# untitled.net
KiCad netlist of a schematic drawn in EAGLE
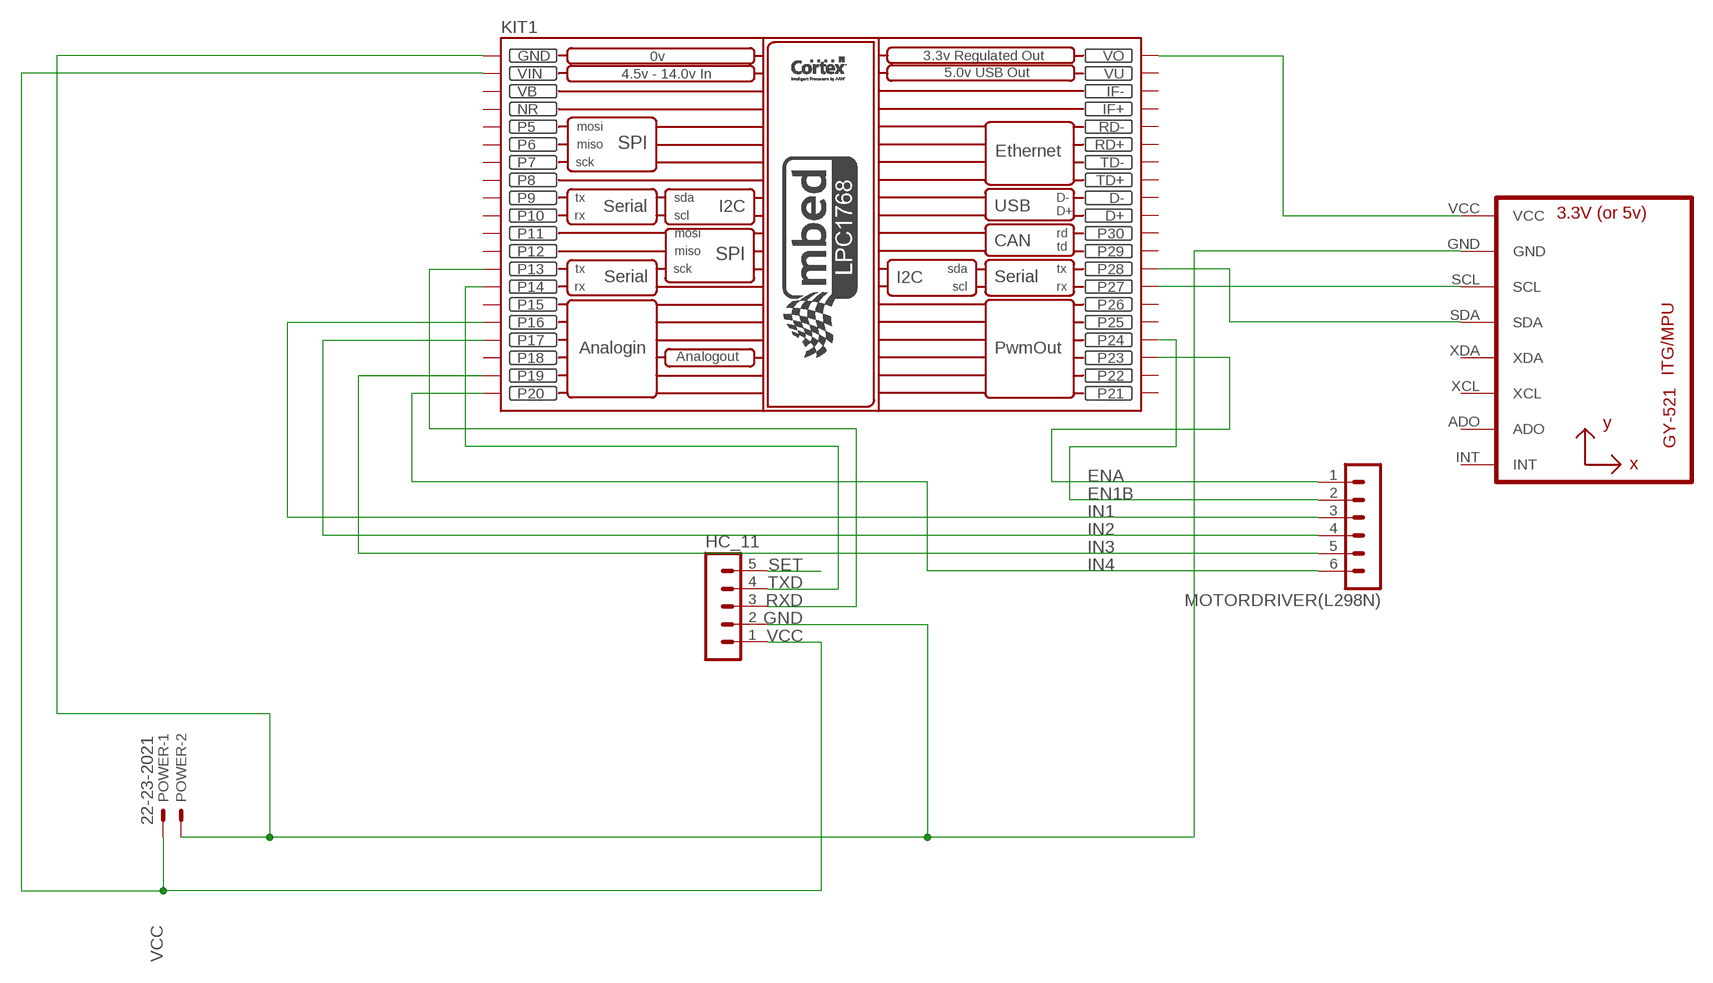
[diagram p0: schematic, sheet 1]

(export (version "E")
  (design (tool "Eeschema 10.0.6"))
  (components
    (comp (ref "HC_11")
      (value "MA05-1")
      (footprint "eagle-import:MA05-1")
      (libsource (lib "eagle-import") (part "MA05-1"))
    )
    (comp (ref "KIT1")
      (value "MBED_NXP_LPC1768")
      (footprint "eagle-import:MBED-KIT")
      (libsource (lib "eagle-import") (part "MBED_NXP_LPC1768"))
    )
    (comp (ref "MOTORDRIVER(L298N)")
      (value "MA06-1")
      (footprint "eagle-import:MA06-1")
      (libsource (lib "eagle-import") (part "MA06-1"))
    )
    (comp (ref "POWER")
      (value "22-23-2021")
      (footprint "eagle-import:22-23-2021")
      (fields (field (name "MF") "MOLEX"))
      (libsource (lib "eagle-import") (part "22-23-2021"))
    )
    (comp (ref "U1")
      (value "GY-521MPU6050")
      (footprint "eagle-import:GY-521")
      (libsource (lib "eagle-import") (part "GY-521MPU6050"))
    )
  )
  (nets
    (net (code "1") (name "/EN1B") (class "Default")
      (node (ref "KIT1") (pin "P$24") (pinfunction "P24_P$24") (pintype "bidirectional"))
      (node (ref "MOTORDRIVER(L298N)") (pin "2") (pinfunction "2_2") (pintype "passive"))
    )
    (net (code "2") (name "/ENA") (class "Default")
      (node (ref "KIT1") (pin "P$23") (pinfunction "P23_P$23") (pintype "bidirectional"))
      (node (ref "MOTORDRIVER(L298N)") (pin "1") (pinfunction "1_1") (pintype "passive"))
    )
    (net (code "3") (name "/GND") (class "Default")
      (node (ref "HC_11") (pin "2") (pinfunction "2_2") (pintype "passive"))
      (node (ref "KIT1") (pin "GND") (pinfunction "GND_GND") (pintype "power_in"))
      (node (ref "POWER") (pin "2") (pinfunction "S_2") (pintype "passive"))
      (node (ref "U1") (pin "GND") (pinfunction "GND_GND") (pintype "bidirectional"))
    )
    (net (code "4") (name "/IN1") (class "Default")
      (node (ref "KIT1") (pin "P$16") (pinfunction "P16_P$16") (pintype "bidirectional"))
      (node (ref "MOTORDRIVER(L298N)") (pin "3") (pinfunction "3_3") (pintype "passive"))
    )
    (net (code "5") (name "/IN2") (class "Default")
      (node (ref "KIT1") (pin "P$17") (pinfunction "P17_P$17") (pintype "bidirectional"))
      (node (ref "MOTORDRIVER(L298N)") (pin "4") (pinfunction "4_4") (pintype "passive"))
    )
    (net (code "6") (name "/IN3") (class "Default")
      (node (ref "KIT1") (pin "P$19") (pinfunction "P19_P$19") (pintype "bidirectional"))
      (node (ref "MOTORDRIVER(L298N)") (pin "5") (pinfunction "5_5") (pintype "passive"))
    )
    (net (code "7") (name "/IN4") (class "Default")
      (node (ref "KIT1") (pin "P$20") (pinfunction "P20_P$20") (pintype "bidirectional"))
      (node (ref "MOTORDRIVER(L298N)") (pin "6") (pinfunction "6_6") (pintype "passive"))
    )
    (net (code "8") (name "/NR") (class "Default")
      (node (ref "KIT1") (pin "NR") (pinfunction "NR_NR") (pintype "power_in"))
    )
    (net (code "9") (name "/RXD") (class "Default")
      (node (ref "HC_11") (pin "3") (pinfunction "3_3") (pintype "passive"))
      (node (ref "KIT1") (pin "P$13") (pinfunction "P13_P$13") (pintype "bidirectional"))
    )
    (net (code "10") (name "/SET") (class "Default")
      (node (ref "HC_11") (pin "5") (pinfunction "5_5") (pintype "passive"))
    )
    (net (code "11") (name "/TXD") (class "Default")
      (node (ref "HC_11") (pin "4") (pinfunction "4_4") (pintype "passive"))
      (node (ref "KIT1") (pin "P$14") (pinfunction "P14_P$14") (pintype "bidirectional"))
    )
    (net (code "12") (name "/VB") (class "Default")
      (node (ref "KIT1") (pin "VB") (pinfunction "VB_VB") (pintype "power_in"))
    )
    (net (code "13") (name "/VCC") (class "Default")
      (node (ref "HC_11") (pin "1") (pinfunction "1_1") (pintype "passive"))
      (node (ref "KIT1") (pin "VIN") (pinfunction "VIN_VIN") (pintype "power_in"))
      (node (ref "POWER") (pin "1") (pinfunction "S_1") (pintype "passive"))
    )
    (net (code "14") (name "/VU") (class "Default")
      (node (ref "KIT1") (pin "VU") (pinfunction "VU_VU") (pintype "power_in"))
    )
    (net (code "15") (name "Net-(KIT1-P27)") (class "Default")
      (node (ref "KIT1") (pin "P$27") (pinfunction "P27_P$27") (pintype "bidirectional"))
      (node (ref "U1") (pin "SCL") (pinfunction "SCL_SCL") (pintype "bidirectional"))
    )
    (net (code "16") (name "Net-(KIT1-P28)") (class "Default")
      (node (ref "KIT1") (pin "P$28") (pinfunction "P28_P$28") (pintype "bidirectional"))
      (node (ref "U1") (pin "SDA") (pinfunction "SDA_SDA") (pintype "bidirectional"))
    )
    (net (code "17") (name "Net-(KIT1-VO)") (class "Default")
      (node (ref "KIT1") (pin "VOUT") (pinfunction "VO_VOUT") (pintype "power_in"))
      (node (ref "U1") (pin "VCC") (pinfunction "VCC_VCC") (pintype "bidirectional"))
    )
    (net (code "18") (name "unconnected-(KIT1-P5-PadP$5)") (class "Default")
      (node (ref "KIT1") (pin "P$5") (pinfunction "P5_P$5") (pintype "bidirectional"))
    )
    (net (code "19") (name "unconnected-(KIT1-P6-PadP$6)") (class "Default")
      (node (ref "KIT1") (pin "P$6") (pinfunction "P6_P$6") (pintype "bidirectional"))
    )
    (net (code "20") (name "unconnected-(KIT1-P7-PadP$7)") (class "Default")
      (node (ref "KIT1") (pin "P$7") (pinfunction "P7_P$7") (pintype "bidirectional"))
    )
    (net (code "21") (name "unconnected-(KIT1-P8-PadP$8)") (class "Default")
      (node (ref "KIT1") (pin "P$8") (pinfunction "P8_P$8") (pintype "bidirectional"))
    )
    (net (code "22") (name "unconnected-(KIT1-P9-PadP$9)") (class "Default")
      (node (ref "KIT1") (pin "P$9") (pinfunction "P9_P$9") (pintype "bidirectional"))
    )
    (net (code "23") (name "unconnected-(KIT1-P10-PadP$10)") (class "Default")
      (node (ref "KIT1") (pin "P$10") (pinfunction "P10_P$10") (pintype "bidirectional"))
    )
    (net (code "24") (name "unconnected-(KIT1-P11-PadP$11)") (class "Default")
      (node (ref "KIT1") (pin "P$11") (pinfunction "P11_P$11") (pintype "bidirectional"))
    )
    (net (code "25") (name "unconnected-(KIT1-P12-PadP$12)") (class "Default")
      (node (ref "KIT1") (pin "P$12") (pinfunction "P12_P$12") (pintype "bidirectional"))
    )
    (net (code "26") (name "unconnected-(KIT1-P15-PadP$15)") (class "Default")
      (node (ref "KIT1") (pin "P$15") (pinfunction "P15_P$15") (pintype "bidirectional"))
    )
    (net (code "27") (name "unconnected-(KIT1-P18-PadP$18)") (class "Default")
      (node (ref "KIT1") (pin "P$18") (pinfunction "P18_P$18") (pintype "bidirectional"))
    )
    (net (code "28") (name "unconnected-(KIT1-P21-PadP$21)") (class "Default")
      (node (ref "KIT1") (pin "P$21") (pinfunction "P21_P$21") (pintype "bidirectional"))
    )
    (net (code "29") (name "unconnected-(KIT1-P22-PadP$22)") (class "Default")
      (node (ref "KIT1") (pin "P$22") (pinfunction "P22_P$22") (pintype "bidirectional"))
    )
    (net (code "30") (name "unconnected-(KIT1-P25-PadP$25)") (class "Default")
      (node (ref "KIT1") (pin "P$25") (pinfunction "P25_P$25") (pintype "bidirectional"))
    )
    (net (code "31") (name "unconnected-(KIT1-P26-PadP$26)") (class "Default")
      (node (ref "KIT1") (pin "P$26") (pinfunction "P26_P$26") (pintype "bidirectional"))
    )
    (net (code "32") (name "unconnected-(KIT1-P29-PadP$29)") (class "Default")
      (node (ref "KIT1") (pin "P$29") (pinfunction "P29_P$29") (pintype "bidirectional"))
    )
    (net (code "33") (name "unconnected-(KIT1-P30-PadP$30)") (class "Default")
      (node (ref "KIT1") (pin "P$30") (pinfunction "P30_P$30") (pintype "bidirectional"))
    )
    (net (code "34") (name "unconnected-(KIT1-PadD+)") (class "Default")
      (node (ref "KIT1") (pin "D+") (pinfunction "D+_D+") (pintype "bidirectional"))
    )
    (net (code "35") (name "unconnected-(KIT1-PadD-)") (class "Default")
      (node (ref "KIT1") (pin "D-") (pinfunction "D-_D-") (pintype "bidirectional"))
    )
    (net (code "36") (name "unconnected-(KIT1-PadIF+)") (class "Default")
      (node (ref "KIT1") (pin "IF+") (pinfunction "IF+_IF+") (pintype "bidirectional"))
    )
    (net (code "37") (name "unconnected-(KIT1-PadIF-)") (class "Default")
      (node (ref "KIT1") (pin "IF-") (pinfunction "IF-_IF-") (pintype "bidirectional"))
    )
    (net (code "38") (name "unconnected-(KIT1-PadRD+)") (class "Default")
      (node (ref "KIT1") (pin "RD+") (pinfunction "RD+_RD+") (pintype "bidirectional"))
    )
    (net (code "39") (name "unconnected-(KIT1-PadRD-)") (class "Default")
      (node (ref "KIT1") (pin "RD-") (pinfunction "RD-_RD-") (pintype "bidirectional"))
    )
    (net (code "40") (name "unconnected-(KIT1-PadTD+)") (class "Default")
      (node (ref "KIT1") (pin "TD+") (pinfunction "TD+_TD+") (pintype "bidirectional"))
    )
    (net (code "41") (name "unconnected-(KIT1-PadTD-)") (class "Default")
      (node (ref "KIT1") (pin "TD-") (pinfunction "TD-_TD-") (pintype "bidirectional"))
    )
    (net (code "42") (name "unconnected-(U1-PadADO)") (class "Default")
      (node (ref "U1") (pin "ADO") (pinfunction "ADO_ADO") (pintype "bidirectional"))
    )
    (net (code "43") (name "unconnected-(U1-PadINT)") (class "Default")
      (node (ref "U1") (pin "INT") (pinfunction "INT_INT") (pintype "bidirectional"))
    )
    (net (code "44") (name "unconnected-(U1-PadXCL)") (class "Default")
      (node (ref "U1") (pin "XCL") (pinfunction "XCL_XCL") (pintype "bidirectional"))
    )
    (net (code "45") (name "unconnected-(U1-PadXDA)") (class "Default")
      (node (ref "U1") (pin "XDA") (pinfunction "XDA_XDA") (pintype "bidirectional"))
    )
  )
)
